# Smart_AC_Monitor.net
KiCad netlist of a schematic drawn in Altium Designer
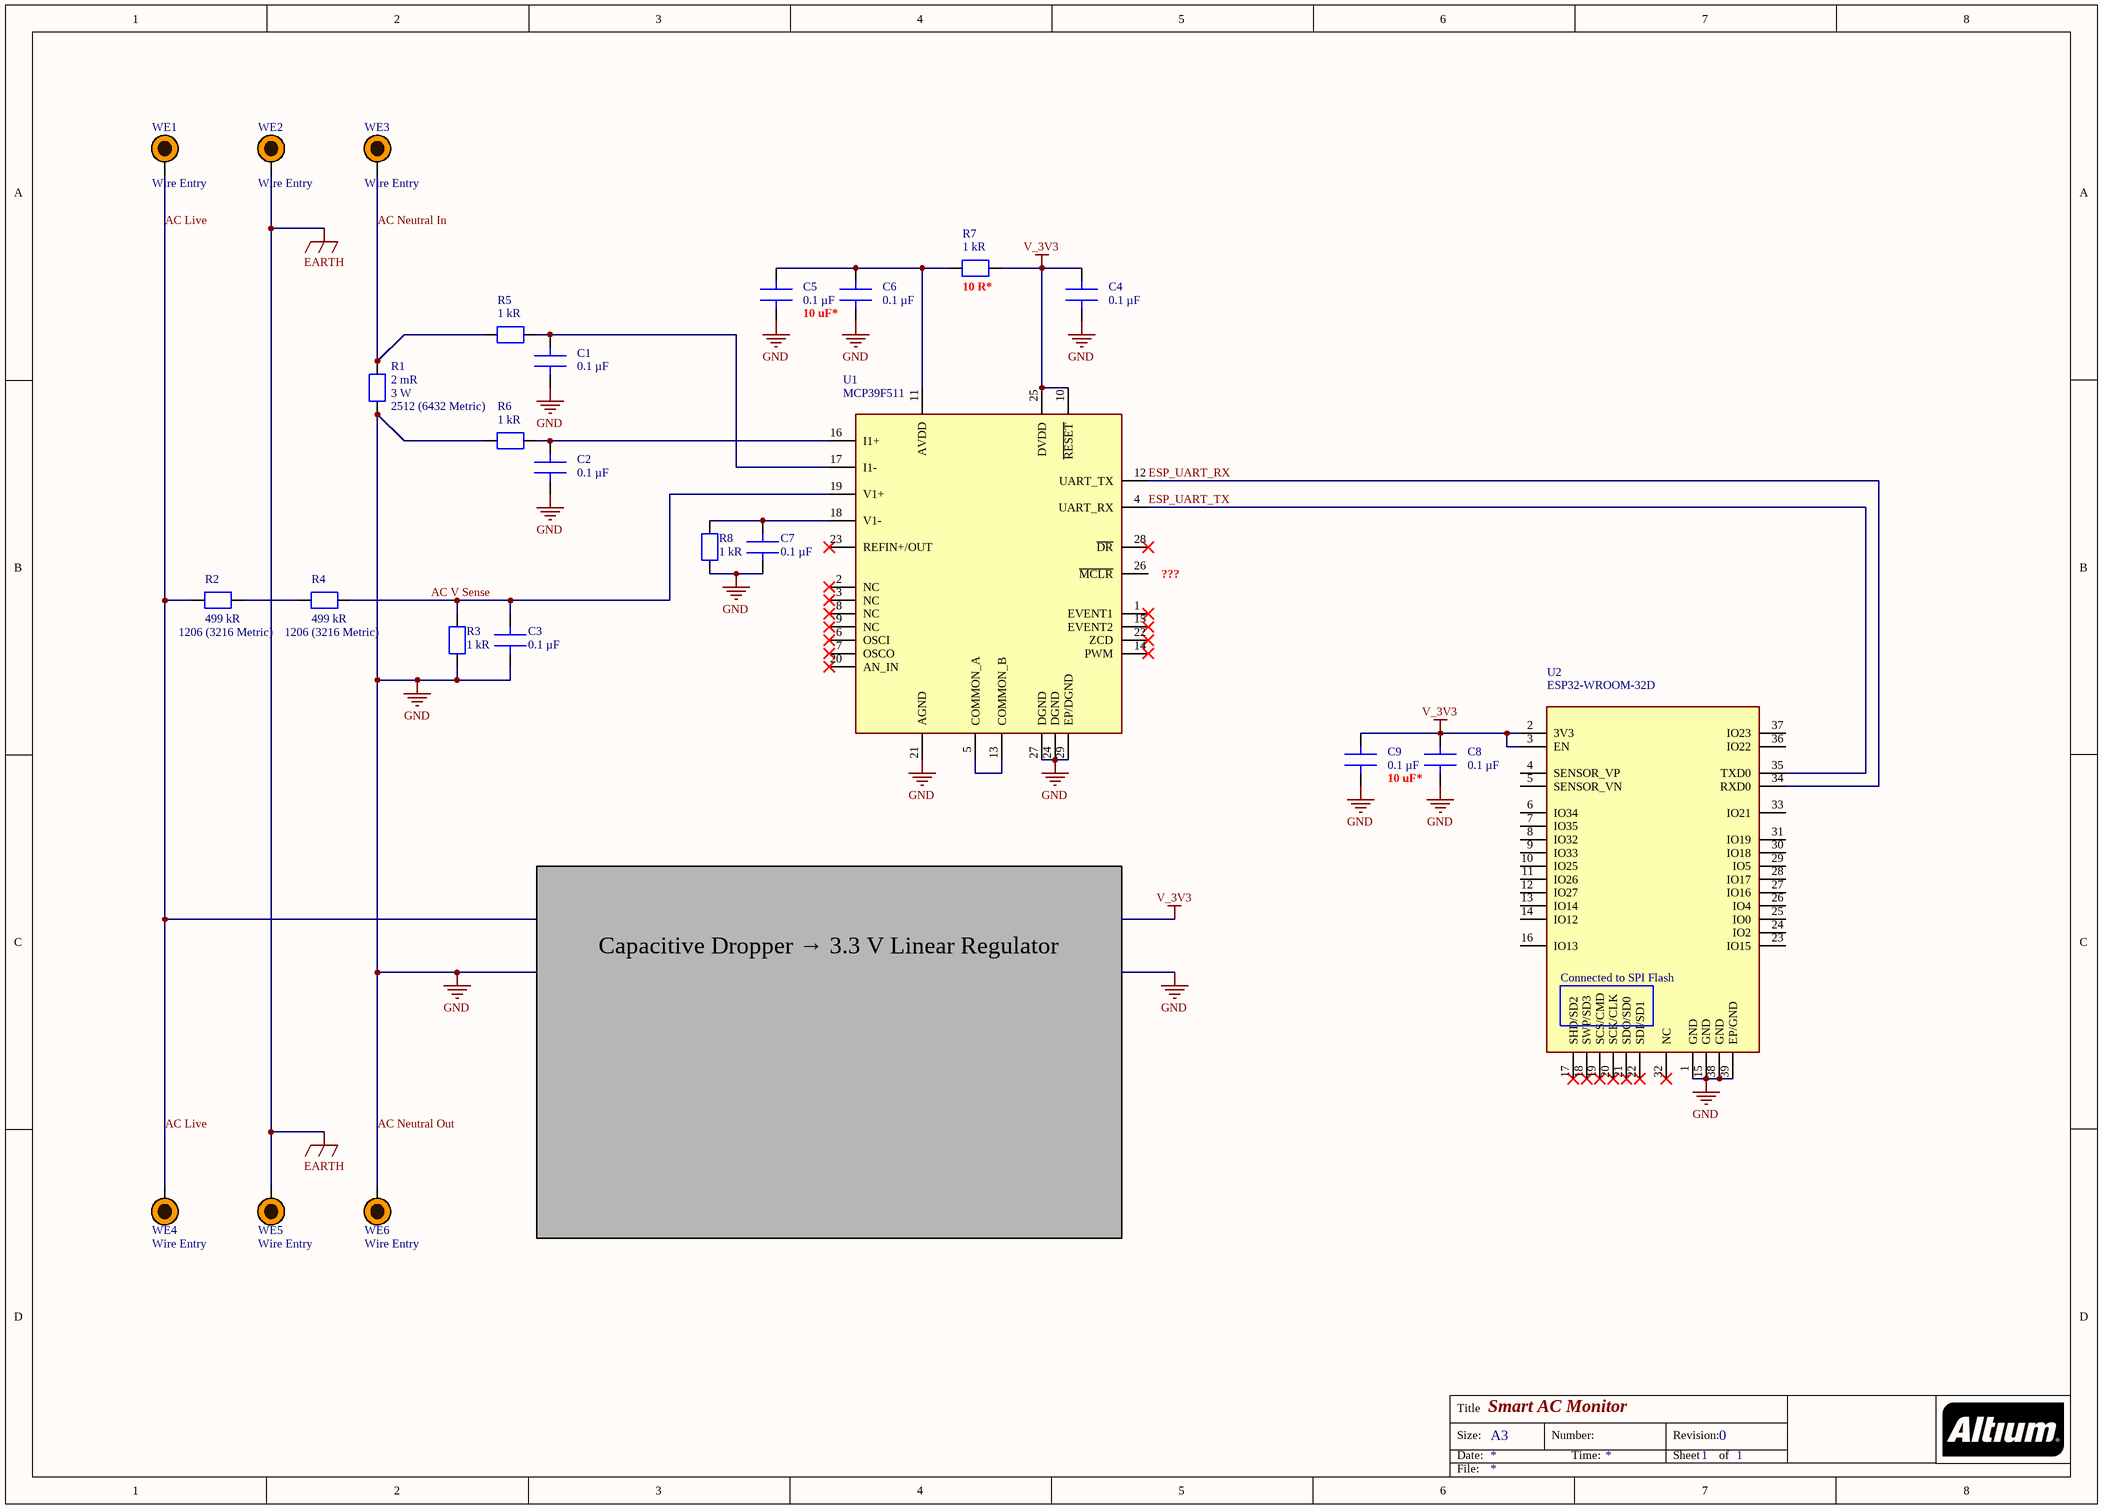
[diagram p0: Smart_AC_Monitor.SchDoc]

(export (version "E")
  (design (tool "Eeschema 10.0.6"))
  (components
    (comp (ref "C1")
      (value "Capacitor")
      (footprint "0805")
      (description "AVX Corporation 08055D104KAT2A")
      (fields
        (field (name "UNIQUE PART NUMBER") "LM_CAP_0001")
        (field (name "DIGIKEY PART NUMBER") "478-12790-1-ND")
        (field (name "CAPACITANCE") "0.1 µF")
      )
      (libsource (lib "Database") (part "Capacitor"))
    )
    (comp (ref "C2")
      (value "Capacitor")
      (footprint "0805")
      (description "AVX Corporation 08055D104KAT2A")
      (fields
        (field (name "UNIQUE PART NUMBER") "LM_CAP_0001")
        (field (name "DIGIKEY PART NUMBER") "478-12790-1-ND")
        (field (name "CAPACITANCE") "0.1 µF")
      )
      (libsource (lib "Database") (part "Capacitor"))
    )
    (comp (ref "C3")
      (value "Capacitor")
      (footprint "0805")
      (description "AVX Corporation 08055D104KAT2A")
      (fields
        (field (name "CAPACITANCE") "0.1 µF")
        (field (name "UNIQUE PART NUMBER") "LM_CAP_0001")
        (field (name "DIGIKEY PART NUMBER") "478-12790-1-ND")
      )
      (libsource (lib "Database") (part "Capacitor"))
    )
    (comp (ref "C4")
      (value "Capacitor")
      (footprint "0805")
      (description "AVX Corporation 08055D104KAT2A")
      (fields
        (field (name "UNIQUE PART NUMBER") "LM_CAP_0001")
        (field (name "DIGIKEY PART NUMBER") "478-12790-1-ND")
        (field (name "CAPACITANCE") "0.1 µF")
      )
      (libsource (lib "Database") (part "Capacitor"))
    )
    (comp (ref "C5")
      (value "Capacitor")
      (footprint "0805")
      (description "AVX Corporation 08055D104KAT2A")
      (fields
        (field (name "UNIQUE PART NUMBER") "LM_CAP_0001")
        (field (name "DIGIKEY PART NUMBER") "478-12790-1-ND")
        (field (name "CAPACITANCE") "0.1 µF")
      )
      (libsource (lib "Database") (part "Capacitor"))
    )
    (comp (ref "C6")
      (value "Capacitor")
      (footprint "0805")
      (description "AVX Corporation 08055D104KAT2A")
      (fields
        (field (name "UNIQUE PART NUMBER") "LM_CAP_0001")
        (field (name "DIGIKEY PART NUMBER") "478-12790-1-ND")
        (field (name "CAPACITANCE") "0.1 µF")
      )
      (libsource (lib "Database") (part "Capacitor"))
    )
    (comp (ref "C7")
      (value "Capacitor")
      (footprint "0805")
      (description "AVX Corporation 08055D104KAT2A")
      (fields
        (field (name "CAPACITANCE") "0.1 µF")
        (field (name "UNIQUE PART NUMBER") "LM_CAP_0001")
        (field (name "DIGIKEY PART NUMBER") "478-12790-1-ND")
      )
      (libsource (lib "Database") (part "Capacitor"))
    )
    (comp (ref "C8")
      (value "Capacitor")
      (footprint "0805")
      (description "AVX Corporation 08055D104KAT2A")
      (fields
        (field (name "UNIQUE PART NUMBER") "LM_CAP_0001")
        (field (name "DIGIKEY PART NUMBER") "478-12790-1-ND")
        (field (name "CAPACITANCE") "0.1 µF")
      )
      (libsource (lib "Database") (part "Capacitor"))
    )
    (comp (ref "C9")
      (value "Capacitor")
      (footprint "0805")
      (description "AVX Corporation 08055D104KAT2A")
      (fields
        (field (name "UNIQUE PART NUMBER") "LM_CAP_0001")
        (field (name "DIGIKEY PART NUMBER") "478-12790-1-ND")
        (field (name "CAPACITANCE") "0.1 µF")
      )
      (libsource (lib "Database") (part "Capacitor"))
    )
    (comp (ref "R1")
      (value "Resistor")
      (footprint "2512")
      (fields
        (field (name "UNIQUE PART NUMBER") "LM_RES_0002")
        (field (name "MANUFACTURER PART NUMBER") "Riedon CSRL3-0R002F8")
        (field (name "DIGIKEY PART NUMBER") "696-1836-1-ND")
        (field (name "RESISTANCE") "2 mR")
        (field (name "POWER") "3 W")
        (field (name "PACKAGE") "2512 (6432 Metric)")
      )
      (libsource (lib "Database") (part "Resistor"))
    )
    (comp (ref "R2")
      (value "Resistor")
      (footprint "1206")
      (fields
        (field (name "UNIQUE PART NUMBER") "LM_RES_0003")
        (field (name "MANUFACTURER PART NUMBER") "Stackpole Electronics Inc RMCF1206FT499K")
        (field (name "DIGIKEY PART NUMBER") "RMCF1206FT499KCT-ND")
        (field (name "RESISTANCE") "499 kR")
        (field (name "PACKAGE") "1206 (3216 Metric)")
      )
      (libsource (lib "Database") (part "Resistor"))
    )
    (comp (ref "R3")
      (value "Resistor")
      (footprint "0805")
      (fields
        (field (name "UNIQUE PART NUMBER") "LM_RES_0001")
        (field (name "MANUFACTURER PART NUMBER") "Stackpole Electronics Inc RMCF0805FT1K00")
        (field (name "DIGIKEY PART NUMBER") "RMCF0805FT1K00CT-ND")
        (field (name "RESISTANCE") "1 kR")
      )
      (libsource (lib "Database") (part "Resistor"))
    )
    (comp (ref "R4")
      (value "Resistor")
      (footprint "1206")
      (fields
        (field (name "UNIQUE PART NUMBER") "LM_RES_0003")
        (field (name "MANUFACTURER PART NUMBER") "Stackpole Electronics Inc RMCF1206FT499K")
        (field (name "DIGIKEY PART NUMBER") "RMCF1206FT499KCT-ND")
        (field (name "RESISTANCE") "499 kR")
        (field (name "PACKAGE") "1206 (3216 Metric)")
      )
      (libsource (lib "Database") (part "Resistor"))
    )
    (comp (ref "R5")
      (value "Resistor")
      (footprint "0805")
      (fields
        (field (name "UNIQUE PART NUMBER") "LM_RES_0001")
        (field (name "MANUFACTURER PART NUMBER") "Stackpole Electronics Inc RMCF0805FT1K00")
        (field (name "DIGIKEY PART NUMBER") "RMCF0805FT1K00CT-ND")
        (field (name "RESISTANCE") "1 kR")
      )
      (libsource (lib "Database") (part "Resistor"))
    )
    (comp (ref "R6")
      (value "Resistor")
      (footprint "0805")
      (fields
        (field (name "UNIQUE PART NUMBER") "LM_RES_0001")
        (field (name "MANUFACTURER PART NUMBER") "Stackpole Electronics Inc RMCF0805FT1K00")
        (field (name "DIGIKEY PART NUMBER") "RMCF0805FT1K00CT-ND")
        (field (name "RESISTANCE") "1 kR")
      )
      (libsource (lib "Database") (part "Resistor"))
    )
    (comp (ref "R7")
      (value "Resistor")
      (footprint "0805")
      (fields
        (field (name "UNIQUE PART NUMBER") "LM_RES_0001")
        (field (name "MANUFACTURER PART NUMBER") "Stackpole Electronics Inc RMCF0805FT1K00")
        (field (name "DIGIKEY PART NUMBER") "RMCF0805FT1K00CT-ND")
        (field (name "RESISTANCE") "1 kR")
      )
      (libsource (lib "Database") (part "Resistor"))
    )
    (comp (ref "R8")
      (value "Resistor")
      (footprint "0805")
      (fields
        (field (name "UNIQUE PART NUMBER") "LM_RES_0001")
        (field (name "MANUFACTURER PART NUMBER") "Stackpole Electronics Inc RMCF0805FT1K00")
        (field (name "DIGIKEY PART NUMBER") "RMCF0805FT1K00CT-ND")
        (field (name "RESISTANCE") "1 kR")
      )
      (libsource (lib "Database") (part "Resistor"))
    )
    (comp (ref "U1")
      (value "MCP39F511")
      (footprint "MCP39F511")
      (description "Single Phase Meter IC 28-QFN (5x5)")
      (fields
        (field (name "UNIQUE PART NUMBER") "LM_IC_0001")
        (field (name "MANUFACTURER PART NUMBER") "Microchip Technology MCP39F511-E/MQ")
      )
      (libsource (lib "Database") (part "MCP39F511"))
    )
    (comp (ref "U2")
      (value "ESP32-WROOM-32D")
      (footprint "ESP32-WROOM-32D")
      (description "Bluetooth, WiFi,3 Transceiver Module")
      (fields
        (field (name "UNIQUE PART NUMBER") "LM_IC_0002")
        (field (name "MANUFACTURER PART NUMBER") "Espressif Systems ESP32-WROOM-32D")
      )
      (libsource (lib "Database") (part "ESP32-WROOM-32D"))
    )
    (comp (ref "WE1")
      (value "Wire Entry")
      (footprint "12AWGWireEntry")
      (description "12 AWG Wire Entry")
      (fields (field (name "UNIQUE PART NUMBER") "LM_OTH_0001"))
      (libsource (lib "Database") (part "Wire Entry"))
    )
    (comp (ref "WE2")
      (value "Wire Entry")
      (footprint "12AWGWireEntry")
      (description "12 AWG Wire Entry")
      (fields (field (name "UNIQUE PART NUMBER") "LM_OTH_0001"))
      (libsource (lib "Database") (part "Wire Entry"))
    )
    (comp (ref "WE3")
      (value "Wire Entry")
      (footprint "12AWGWireEntry")
      (description "12 AWG Wire Entry")
      (fields (field (name "UNIQUE PART NUMBER") "LM_OTH_0001"))
      (libsource (lib "Database") (part "Wire Entry"))
    )
    (comp (ref "WE4")
      (value "Wire Entry")
      (footprint "12AWGWireEntry")
      (description "12 AWG Wire Entry")
      (fields (field (name "UNIQUE PART NUMBER") "LM_OTH_0001"))
      (libsource (lib "Database") (part "Wire Entry"))
    )
    (comp (ref "WE5")
      (value "Wire Entry")
      (footprint "12AWGWireEntry")
      (description "12 AWG Wire Entry")
      (fields (field (name "UNIQUE PART NUMBER") "LM_OTH_0001"))
      (libsource (lib "Database") (part "Wire Entry"))
    )
    (comp (ref "WE6")
      (value "Wire Entry")
      (footprint "12AWGWireEntry")
      (description "12 AWG Wire Entry")
      (fields (field (name "UNIQUE PART NUMBER") "LM_OTH_0001"))
      (libsource (lib "Database") (part "Wire Entry"))
    )
  )
  (nets
    (net (code "1") (name "/AC Live") (class "Default")
      (node (ref "R2") (pin "1") (pinfunction "1_1") (pintype "passive"))
      (node (ref "WE1") (pin "1") (pinfunction "1_1") (pintype "passive"))
      (node (ref "WE4") (pin "1") (pinfunction "1_1") (pintype "passive"))
    )
    (net (code "2") (name "/AC Neutral In") (class "Default")
      (node (ref "R1") (pin "1") (pinfunction "1_1") (pintype "passive"))
      (node (ref "R5") (pin "1") (pinfunction "1_1") (pintype "passive"))
      (node (ref "WE3") (pin "1") (pinfunction "1_1") (pintype "passive"))
    )
    (net (code "3") (name "/AC V Sense") (class "Default")
      (node (ref "C3") (pin "1") (pinfunction "1_1") (pintype "passive"))
      (node (ref "R3") (pin "1") (pinfunction "1_1") (pintype "passive"))
      (node (ref "R4") (pin "2") (pinfunction "2_2") (pintype "passive"))
      (node (ref "U1") (pin "19") (pinfunction "V1+_19") (pintype "passive"))
    )
    (net (code "4") (name "/ESP_UART_RX") (class "Default")
      (node (ref "U1") (pin "12") (pinfunction "UART_TX_12") (pintype "passive"))
      (node (ref "U2") (pin "34") (pinfunction "RXD0_34") (pintype "passive"))
    )
    (net (code "5") (name "/ESP_UART_TX") (class "Default")
      (node (ref "U1") (pin "4") (pinfunction "UART_RX_4") (pintype "passive"))
      (node (ref "U2") (pin "35") (pinfunction "TXD0_35") (pintype "passive"))
    )
    (net (code "6") (name "EARTH") (class "Default")
      (node (ref "WE2") (pin "1") (pinfunction "1_1") (pintype "passive"))
      (node (ref "WE5") (pin "1") (pinfunction "1_1") (pintype "passive"))
    )
    (net (code "7") (name "GND") (class "Default")
      (node (ref "C1") (pin "2") (pinfunction "2_2") (pintype "passive"))
      (node (ref "C2") (pin "2") (pinfunction "2_2") (pintype "passive"))
      (node (ref "C3") (pin "2") (pinfunction "2_2") (pintype "passive"))
      (node (ref "C4") (pin "2") (pinfunction "2_2") (pintype "passive"))
      (node (ref "C5") (pin "2") (pinfunction "2_2") (pintype "passive"))
      (node (ref "C6") (pin "2") (pinfunction "2_2") (pintype "passive"))
      (node (ref "C7") (pin "2") (pinfunction "2_2") (pintype "passive"))
      (node (ref "C8") (pin "2") (pinfunction "2_2") (pintype "passive"))
      (node (ref "C9") (pin "2") (pinfunction "2_2") (pintype "passive"))
      (node (ref "R1") (pin "2") (pinfunction "2_2") (pintype "passive"))
      (node (ref "R3") (pin "2") (pinfunction "2_2") (pintype "passive"))
      (node (ref "R6") (pin "1") (pinfunction "1_1") (pintype "passive"))
      (node (ref "R8") (pin "1") (pinfunction "1_1") (pintype "passive"))
      (node (ref "U1") (pin "21") (pinfunction "AGND_21") (pintype "passive"))
      (node (ref "U1") (pin "24") (pinfunction "DGND_24") (pintype "passive"))
      (node (ref "U1") (pin "27") (pinfunction "DGND_27") (pintype "passive"))
      (node (ref "U1") (pin "29") (pinfunction "EP/DGND_29") (pintype "passive"))
      (node (ref "U2") (pin "1") (pinfunction "GND_1") (pintype "passive"))
      (node (ref "U2") (pin "15") (pinfunction "GND_15") (pintype "passive"))
      (node (ref "U2") (pin "38") (pinfunction "GND_38") (pintype "passive"))
      (node (ref "U2") (pin "39") (pinfunction "EP/GND_39") (pintype "passive"))
      (node (ref "WE6") (pin "1") (pinfunction "1_1") (pintype "passive"))
    )
    (net (code "8") (name "Net-(R2-Pad2)") (class "Default")
      (node (ref "R2") (pin "2") (pinfunction "2_2") (pintype "passive"))
      (node (ref "R4") (pin "1") (pinfunction "1_1") (pintype "passive"))
    )
    (net (code "9") (name "Net-(U1-AVDD)") (class "Default")
      (node (ref "C5") (pin "1") (pinfunction "1_1") (pintype "passive"))
      (node (ref "C6") (pin "1") (pinfunction "1_1") (pintype "passive"))
      (node (ref "R7") (pin "1") (pinfunction "1_1") (pintype "passive"))
      (node (ref "U1") (pin "11") (pinfunction "AVDD_11") (pintype "passive"))
    )
    (net (code "10") (name "Net-(U1-COMMON_A)") (class "Default")
      (node (ref "U1") (pin "13") (pinfunction "COMMON_B_13") (pintype "passive"))
      (node (ref "U1") (pin "5") (pinfunction "COMMON_A_5") (pintype "passive"))
    )
    (net (code "11") (name "Net-(U1-I1+)") (class "Default")
      (node (ref "C2") (pin "1") (pinfunction "1_1") (pintype "passive"))
      (node (ref "R6") (pin "2") (pinfunction "2_2") (pintype "passive"))
      (node (ref "U1") (pin "16") (pinfunction "I1+_16") (pintype "passive"))
    )
    (net (code "12") (name "Net-(U1-I1-)") (class "Default")
      (node (ref "C1") (pin "1") (pinfunction "1_1") (pintype "passive"))
      (node (ref "R5") (pin "2") (pinfunction "2_2") (pintype "passive"))
      (node (ref "U1") (pin "17") (pinfunction "I1-_17") (pintype "passive"))
    )
    (net (code "13") (name "Net-(U1-V1-)") (class "Default")
      (node (ref "C7") (pin "1") (pinfunction "1_1") (pintype "passive"))
      (node (ref "R8") (pin "2") (pinfunction "2_2") (pintype "passive"))
      (node (ref "U1") (pin "18") (pinfunction "V1-_18") (pintype "passive"))
    )
    (net (code "14") (name "V_3V3") (class "Default")
      (node (ref "C4") (pin "1") (pinfunction "1_1") (pintype "passive"))
      (node (ref "C8") (pin "1") (pinfunction "1_1") (pintype "passive"))
      (node (ref "C9") (pin "1") (pinfunction "1_1") (pintype "passive"))
      (node (ref "R7") (pin "2") (pinfunction "2_2") (pintype "passive"))
      (node (ref "U1") (pin "10") (pinfunction "~{RESET}_10") (pintype "passive"))
      (node (ref "U1") (pin "25") (pinfunction "DVDD_25") (pintype "passive"))
      (node (ref "U2") (pin "2") (pinfunction "3V3_2") (pintype "passive"))
      (node (ref "U2") (pin "3") (pinfunction "EN_3") (pintype "passive"))
    )
    (net (code "15") (name "unconnected-(U1-AN_IN-Pad20)") (class "Default")
      (node (ref "U1") (pin "20") (pinfunction "AN_IN_20") (pintype "passive+no_connect"))
    )
    (net (code "16") (name "unconnected-(U1-EVENT1-Pad1)") (class "Default")
      (node (ref "U1") (pin "1") (pinfunction "EVENT1_1") (pintype "passive+no_connect"))
    )
    (net (code "17") (name "unconnected-(U1-EVENT2-Pad15)") (class "Default")
      (node (ref "U1") (pin "15") (pinfunction "EVENT2_15") (pintype "passive+no_connect"))
    )
    (net (code "18") (name "unconnected-(U1-NC-Pad2)") (class "Default")
      (node (ref "U1") (pin "2") (pinfunction "NC_2") (pintype "passive+no_connect"))
    )
    (net (code "19") (name "unconnected-(U1-NC-Pad3)") (class "Default")
      (node (ref "U1") (pin "3") (pinfunction "NC_3") (pintype "passive+no_connect"))
    )
    (net (code "20") (name "unconnected-(U1-NC-Pad8)") (class "Default")
      (node (ref "U1") (pin "8") (pinfunction "NC_8") (pintype "passive+no_connect"))
    )
    (net (code "21") (name "unconnected-(U1-NC-Pad9)") (class "Default")
      (node (ref "U1") (pin "9") (pinfunction "NC_9") (pintype "passive+no_connect"))
    )
    (net (code "22") (name "unconnected-(U1-OSCI-Pad6)") (class "Default")
      (node (ref "U1") (pin "6") (pinfunction "OSCI_6") (pintype "passive+no_connect"))
    )
    (net (code "23") (name "unconnected-(U1-OSCO-Pad7)") (class "Default")
      (node (ref "U1") (pin "7") (pinfunction "OSCO_7") (pintype "passive+no_connect"))
    )
    (net (code "24") (name "unconnected-(U1-PWM-Pad14)") (class "Default")
      (node (ref "U1") (pin "14") (pinfunction "PWM_14") (pintype "passive+no_connect"))
    )
    (net (code "25") (name "unconnected-(U1-REFIN+{slash}OUT-Pad23)") (class "Default")
      (node (ref "U1") (pin "23") (pinfunction "REFIN+/OUT_23") (pintype "passive+no_connect"))
    )
    (net (code "26") (name "unconnected-(U1-ZCD-Pad22)") (class "Default")
      (node (ref "U1") (pin "22") (pinfunction "ZCD_22") (pintype "passive+no_connect"))
    )
    (net (code "27") (name "unconnected-(U1-~{DR}-Pad28)") (class "Default")
      (node (ref "U1") (pin "28") (pinfunction "~{DR}_28") (pintype "passive+no_connect"))
    )
    (net (code "28") (name "unconnected-(U1-~{MCLR}-Pad26)") (class "Default")
      (node (ref "U1") (pin "26") (pinfunction "~{MCLR}_26") (pintype "passive"))
    )
    (net (code "29") (name "unconnected-(U2-IO0-Pad25)") (class "Default")
      (node (ref "U2") (pin "25") (pinfunction "IO0_25") (pintype "passive"))
    )
    (net (code "30") (name "unconnected-(U2-IO2-Pad24)") (class "Default")
      (node (ref "U2") (pin "24") (pinfunction "IO2_24") (pintype "passive"))
    )
    (net (code "31") (name "unconnected-(U2-IO4-Pad26)") (class "Default")
      (node (ref "U2") (pin "26") (pinfunction "IO4_26") (pintype "passive"))
    )
    (net (code "32") (name "unconnected-(U2-IO5-Pad29)") (class "Default")
      (node (ref "U2") (pin "29") (pinfunction "IO5_29") (pintype "passive"))
    )
    (net (code "33") (name "unconnected-(U2-IO12-Pad14)") (class "Default")
      (node (ref "U2") (pin "14") (pinfunction "IO12_14") (pintype "passive"))
    )
    (net (code "34") (name "unconnected-(U2-IO13-Pad16)") (class "Default")
      (node (ref "U2") (pin "16") (pinfunction "IO13_16") (pintype "passive"))
    )
    (net (code "35") (name "unconnected-(U2-IO14-Pad13)") (class "Default")
      (node (ref "U2") (pin "13") (pinfunction "IO14_13") (pintype "passive"))
    )
    (net (code "36") (name "unconnected-(U2-IO15-Pad23)") (class "Default")
      (node (ref "U2") (pin "23") (pinfunction "IO15_23") (pintype "passive"))
    )
    (net (code "37") (name "unconnected-(U2-IO16-Pad27)") (class "Default")
      (node (ref "U2") (pin "27") (pinfunction "IO16_27") (pintype "passive"))
    )
    (net (code "38") (name "unconnected-(U2-IO17-Pad28)") (class "Default")
      (node (ref "U2") (pin "28") (pinfunction "IO17_28") (pintype "passive"))
    )
    (net (code "39") (name "unconnected-(U2-IO18-Pad30)") (class "Default")
      (node (ref "U2") (pin "30") (pinfunction "IO18_30") (pintype "passive"))
    )
    (net (code "40") (name "unconnected-(U2-IO19-Pad31)") (class "Default")
      (node (ref "U2") (pin "31") (pinfunction "IO19_31") (pintype "passive"))
    )
    (net (code "41") (name "unconnected-(U2-IO21-Pad33)") (class "Default")
      (node (ref "U2") (pin "33") (pinfunction "IO21_33") (pintype "passive"))
    )
    (net (code "42") (name "unconnected-(U2-IO22-Pad36)") (class "Default")
      (node (ref "U2") (pin "36") (pinfunction "IO22_36") (pintype "passive"))
    )
    (net (code "43") (name "unconnected-(U2-IO23-Pad37)") (class "Default")
      (node (ref "U2") (pin "37") (pinfunction "IO23_37") (pintype "passive"))
    )
    (net (code "44") (name "unconnected-(U2-IO25-Pad10)") (class "Default")
      (node (ref "U2") (pin "10") (pinfunction "IO25_10") (pintype "passive"))
    )
    (net (code "45") (name "unconnected-(U2-IO26-Pad11)") (class "Default")
      (node (ref "U2") (pin "11") (pinfunction "IO26_11") (pintype "passive"))
    )
    (net (code "46") (name "unconnected-(U2-IO27-Pad12)") (class "Default")
      (node (ref "U2") (pin "12") (pinfunction "IO27_12") (pintype "passive"))
    )
    (net (code "47") (name "unconnected-(U2-IO32-Pad8)") (class "Default")
      (node (ref "U2") (pin "8") (pinfunction "IO32_8") (pintype "passive"))
    )
    (net (code "48") (name "unconnected-(U2-IO33-Pad9)") (class "Default")
      (node (ref "U2") (pin "9") (pinfunction "IO33_9") (pintype "passive"))
    )
    (net (code "49") (name "unconnected-(U2-IO34-Pad6)") (class "Default")
      (node (ref "U2") (pin "6") (pinfunction "IO34_6") (pintype "passive"))
    )
    (net (code "50") (name "unconnected-(U2-IO35-Pad7)") (class "Default")
      (node (ref "U2") (pin "7") (pinfunction "IO35_7") (pintype "passive"))
    )
    (net (code "51") (name "unconnected-(U2-NC-Pad32)") (class "Default")
      (node (ref "U2") (pin "32") (pinfunction "NC_32") (pintype "passive+no_connect"))
    )
    (net (code "52") (name "unconnected-(U2-SCK{slash}CLK-Pad20)") (class "Default")
      (node (ref "U2") (pin "20") (pinfunction "SCK/CLK_20") (pintype "passive+no_connect"))
    )
    (net (code "53") (name "unconnected-(U2-SCS{slash}CMD-Pad19)") (class "Default")
      (node (ref "U2") (pin "19") (pinfunction "SCS/CMD_19") (pintype "passive+no_connect"))
    )
    (net (code "54") (name "unconnected-(U2-SDI{slash}SD1-Pad22)") (class "Default")
      (node (ref "U2") (pin "22") (pinfunction "SDI/SD1_22") (pintype "passive+no_connect"))
    )
    (net (code "55") (name "unconnected-(U2-SDO{slash}SD0-Pad21)") (class "Default")
      (node (ref "U2") (pin "21") (pinfunction "SDO/SD0_21") (pintype "passive+no_connect"))
    )
    (net (code "56") (name "unconnected-(U2-SENSOR_VN-Pad5)") (class "Default")
      (node (ref "U2") (pin "5") (pinfunction "SENSOR_VN_5") (pintype "passive"))
    )
    (net (code "57") (name "unconnected-(U2-SENSOR_VP-Pad4)") (class "Default")
      (node (ref "U2") (pin "4") (pinfunction "SENSOR_VP_4") (pintype "passive"))
    )
    (net (code "58") (name "unconnected-(U2-SHD{slash}SD2-Pad17)") (class "Default")
      (node (ref "U2") (pin "17") (pinfunction "SHD/SD2_17") (pintype "passive+no_connect"))
    )
    (net (code "59") (name "unconnected-(U2-SWP{slash}SD3-Pad18)") (class "Default")
      (node (ref "U2") (pin "18") (pinfunction "SWP/SD3_18") (pintype "passive+no_connect"))
    )
  )
)
